# ESP32_S3.net
KiCad netlist of a schematic drawn in Altium Designer
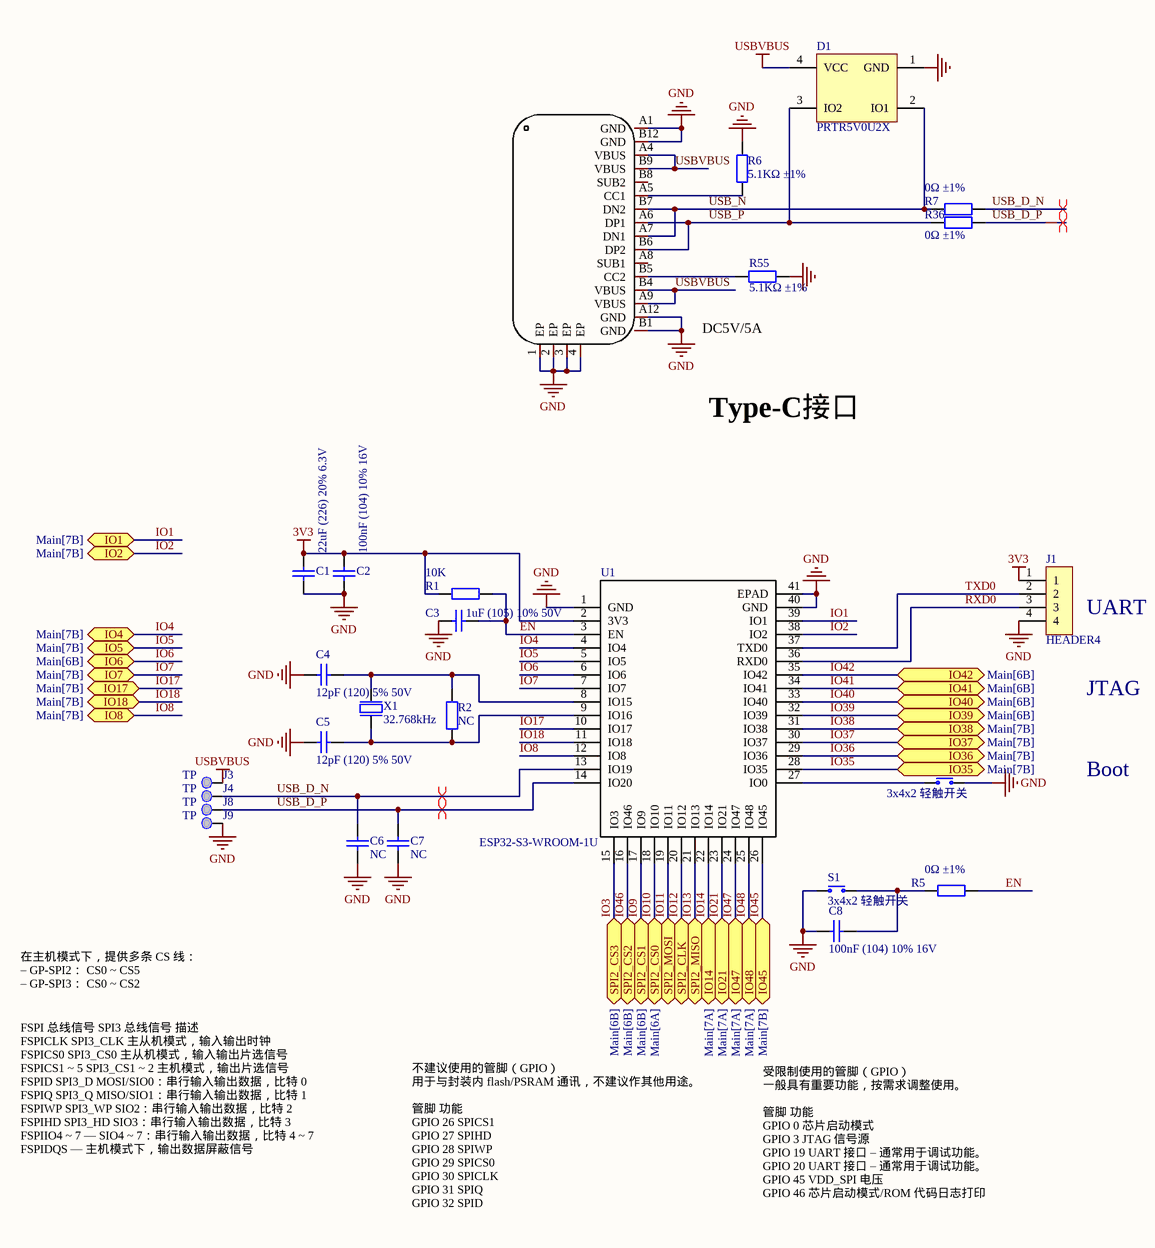
[diagram p0: ESP32_S3.SchDoc]

(export (version "E")
  (design (tool "Eeschema 10.0.6"))
  (components
    (comp (ref "C1")
      (value "22uF (226) 20% 6.3V")
      (footprint "0402_C")
      (description "贴片电容")
      (libsource (lib "Cap") (part "0603 22uF (226) 20% 6.3V"))
    )
    (comp (ref "C2")
      (value "100nF (104) 10% 16V")
      (footprint "0201_C")
      (description "贴片电容")
      (libsource (lib "Cap") (part "0402 100nF (104) 10% 16V"))
    )
    (comp (ref "C3")
      (value "1uF (105) 10% 50V")
      (footprint "0201_C")
      (description "贴片电容")
      (libsource (lib "Cap") (part "0603 1uF (105) 10% 50V"))
    )
    (comp (ref "C4")
      (value "12pF (120) 5% 50V")
      (footprint "0201_C")
      (description "贴片电容")
      (libsource (lib "Cap") (part "0402 12pF (120) 5% 50V"))
    )
    (comp (ref "C5")
      (value "12pF (120) 5% 50V")
      (footprint "0201_C")
      (description "贴片电容")
      (libsource (lib "Cap") (part "0402 12pF (120) 5% 50V"))
    )
    (comp (ref "C6")
      (value "NC")
      (footprint "0402_C")
      (description "贴片电容")
      (libsource (lib "Cap") (part "0402 12pF (120) 5% 50V"))
    )
    (comp (ref "C7")
      (value "NC")
      (footprint "0402_C")
      (description "贴片电容")
      (libsource (lib "Cap") (part "0402 12pF (120) 5% 50V"))
    )
    (comp (ref "C8")
      (value "100nF (104) 10% 16V")
      (footprint "0201_C")
      (description "贴片电容")
      (libsource (lib "Cap") (part "0402 100nF (104) 10% 16V"))
    )
    (comp (ref "D1")
      (value "PRTR5V0U2X")
      (footprint "SOT190P230X110-4L")
      (description "Ultra low capacitance double rail-to-rail ESD protection diode")
      (fields
        (field (name "MANUFACTURER") "NXP")
        (field (name "2ND SOURCE PART NUMBER") "152-4157")
        (field (name "PUBLISHER") "Nordic Semiconductor")
      )
      (libsource (lib "Nordic Discrete DB") (part "PRTR5V0U2X"))
    )
    (comp (ref "J1")
      (value "HEADER4")
      (footprint "HEADER4_2.54MM_排针")
      (libsource (lib "RFID") (part "HEADER4"))
    )
    (comp (ref "J3") (value "TP") (footprint "TEST_Point") (libsource (lib "RFID") (part "TestPad")))
    (comp (ref "J4") (value "TP") (footprint "TEST_Point") (libsource (lib "RFID") (part "TestPad")))
    (comp (ref "J8") (value "TP") (footprint "TEST_Point") (libsource (lib "RFID") (part "TestPad")))
    (comp (ref "J9") (value "TP") (footprint "TEST_Point") (libsource (lib "RFID") (part "TestPad")))
    (comp (ref "R1")
      (value "10K")
      (footprint "0201_R")
      (description "贴片电阻")
      (libsource (lib "RES") (part "0402 10KΩ (1002) 1%"))
    )
    (comp (ref "R2")
      (value "NC")
      (footprint "0402_R")
      (description "贴片电阻")
      (libsource (lib "") (part "0402 10KΩ (1002) 1%_1"))
    )
    (comp (ref "R5")
      (value "0Ω ±1%")
      (footprint "0402_R")
      (description "贴片电阻")
      (libsource (lib "RES") (part "0402 0Ω (0R0) 1%"))
    )
    (comp (ref "R6")
      (value "5.1KΩ ±1%")
      (footprint "0402_R")
      (description "贴片电阻")
      (libsource (lib "Miscellaneous Devices LC") (part "0402 5.1KΩ (5101) 1%"))
    )
    (comp (ref "R7")
      (value "0Ω ±1%")
      (footprint "0402_R")
      (description "贴片电阻")
      (libsource (lib "RES") (part "0402 0Ω (0R0) 1%"))
    )
    (comp (ref "R36")
      (value "0Ω ±1%")
      (footprint "0402_R")
      (description "贴片电阻")
      (libsource (lib "RES") (part "0402 0Ω (0R0) 1%"))
    )
    (comp (ref "R55")
      (value "5.1KΩ ±1%")
      (footprint "0402_R")
      (description "贴片电阻")
      (libsource (lib "") (part "0402 5.1KΩ (5101) 1%_1"))
    )
    (comp (ref "S1")
      (value "3x4x2 轻触开关")
      (footprint "KEY_3x4X2包脚U型")
      (libsource (lib "RFID") (part "SW-PB_包脚U型小乌龟"))
    )
    (comp (ref "S3")
      (value "3x4x2 轻触开关")
      (footprint "KEY_3x4X2包脚U型")
      (libsource (lib "RFID") (part "SW-PB_包脚U型小乌龟"))
    )
    (comp (ref "U1")
      (value "ESP32-S3-WROOM-1U")
      (footprint "WIRELM-SMD_ESP32-S3-WROOM-1U")
      (libsource (lib "RFID") (part "ESP32-S3-WROOM-1U"))
    )
    (comp (ref "USB1")
      (value "KH-TYPE-C-16P")
      (footprint "USB-C-SMD_KH-TYPE-C-16P")
      (libsource (lib "RFID") (part "KH-TYPE-C-16P"))
    )
    (comp (ref "X1")
      (value "32.768kHz")
      (footprint "XTAL_3215")
      (description "XTAL SMD 3215, 32.768kHz, Cl=9pF, Total Tol: ±50ppm")
      (fields (field (name "PART NUMBER") "XTAL_SMD3215_32.768kHz_9pF_General"))
      (libsource (lib "AltiumLib") (part "XTAL_2-pin"))
    )
  )
  (nets
    (net (code "1") (name "/EN") (class "Default")
      (node (ref "C3") (pin "2") (pinfunction "2_2") (pintype "passive"))
      (node (ref "R1") (pin "1") (pinfunction "1_1") (pintype "passive"))
      (node (ref "R5") (pin "2") (pinfunction "2_2") (pintype "passive"))
      (node (ref "U1") (pin "3") (pinfunction "EN_3") (pintype "passive"))
    )
    (net (code "2") (name "/IO1") (class "Default")
      (node (ref "U1") (pin "39") (pinfunction "IO1_39") (pintype "passive"))
    )
    (net (code "3") (name "/IO2") (class "Default")
      (node (ref "U1") (pin "38") (pinfunction "IO2_38") (pintype "passive"))
    )
    (net (code "4") (name "/IO3") (class "Default")
      (node (ref "U1") (pin "15") (pinfunction "IO3_15") (pintype "passive"))
    )
    (net (code "5") (name "/IO4") (class "Default")
      (node (ref "U1") (pin "4") (pinfunction "IO4_4") (pintype "passive"))
    )
    (net (code "6") (name "/IO5") (class "Default")
      (node (ref "U1") (pin "5") (pinfunction "IO5_5") (pintype "passive"))
    )
    (net (code "7") (name "/IO6") (class "Default")
      (node (ref "U1") (pin "6") (pinfunction "IO6_6") (pintype "passive"))
    )
    (net (code "8") (name "/IO7") (class "Default")
      (node (ref "U1") (pin "7") (pinfunction "IO7_7") (pintype "passive"))
    )
    (net (code "9") (name "/IO8") (class "Default")
      (node (ref "U1") (pin "12") (pinfunction "IO8_12") (pintype "passive"))
    )
    (net (code "10") (name "/IO9") (class "Default")
      (node (ref "U1") (pin "17") (pinfunction "IO9_17") (pintype "passive"))
    )
    (net (code "11") (name "/IO10") (class "Default")
      (node (ref "U1") (pin "18") (pinfunction "IO10_18") (pintype "passive"))
    )
    (net (code "12") (name "/IO11") (class "Default")
      (node (ref "U1") (pin "19") (pinfunction "IO11_19") (pintype "passive"))
    )
    (net (code "13") (name "/IO12") (class "Default")
      (node (ref "U1") (pin "20") (pinfunction "IO12_20") (pintype "passive"))
    )
    (net (code "14") (name "/IO13") (class "Default")
      (node (ref "U1") (pin "21") (pinfunction "IO13_21") (pintype "passive"))
    )
    (net (code "15") (name "/IO14") (class "Default")
      (node (ref "U1") (pin "22") (pinfunction "IO14_22") (pintype "passive"))
    )
    (net (code "16") (name "/IO17") (class "Default")
      (node (ref "U1") (pin "10") (pinfunction "IO17_10") (pintype "passive"))
    )
    (net (code "17") (name "/IO18") (class "Default")
      (node (ref "U1") (pin "11") (pinfunction "IO18_11") (pintype "passive"))
    )
    (net (code "18") (name "/IO21") (class "Default")
      (node (ref "U1") (pin "23") (pinfunction "IO21_23") (pintype "passive"))
    )
    (net (code "19") (name "/IO35") (class "Default")
      (node (ref "U1") (pin "28") (pinfunction "IO35_28") (pintype "passive"))
    )
    (net (code "20") (name "/IO36") (class "Default")
      (node (ref "U1") (pin "29") (pinfunction "IO36_29") (pintype "passive"))
    )
    (net (code "21") (name "/IO37") (class "Default")
      (node (ref "U1") (pin "30") (pinfunction "IO37_30") (pintype "passive"))
    )
    (net (code "22") (name "/IO38") (class "Default")
      (node (ref "U1") (pin "31") (pinfunction "IO38_31") (pintype "passive"))
    )
    (net (code "23") (name "/IO39") (class "Default")
      (node (ref "U1") (pin "32") (pinfunction "IO39_32") (pintype "passive"))
    )
    (net (code "24") (name "/IO40") (class "Default")
      (node (ref "U1") (pin "33") (pinfunction "IO40_33") (pintype "passive"))
    )
    (net (code "25") (name "/IO41") (class "Default")
      (node (ref "U1") (pin "34") (pinfunction "IO41_34") (pintype "passive"))
    )
    (net (code "26") (name "/IO42") (class "Default")
      (node (ref "U1") (pin "35") (pinfunction "IO42_35") (pintype "passive"))
    )
    (net (code "27") (name "/IO45") (class "Default")
      (node (ref "U1") (pin "26") (pinfunction "IO45_26") (pintype "passive"))
    )
    (net (code "28") (name "/IO46") (class "Default")
      (node (ref "U1") (pin "16") (pinfunction "IO46_16") (pintype "passive"))
    )
    (net (code "29") (name "/IO47") (class "Default")
      (node (ref "U1") (pin "24") (pinfunction "IO47_24") (pintype "passive"))
    )
    (net (code "30") (name "/IO48") (class "Default")
      (node (ref "U1") (pin "25") (pinfunction "IO48_25") (pintype "passive"))
    )
    (net (code "31") (name "/RXD0") (class "Default")
      (node (ref "J1") (pin "3") (pinfunction "3_3") (pintype "power_in"))
      (node (ref "U1") (pin "36") (pinfunction "RXD0_36") (pintype "passive"))
    )
    (net (code "32") (name "/TXD0") (class "Default")
      (node (ref "J1") (pin "2") (pinfunction "2_2") (pintype "power_in"))
      (node (ref "U1") (pin "37") (pinfunction "TXD0_37") (pintype "passive"))
    )
    (net (code "33") (name "/USB_D_N") (class "Default")
      (node (ref "C6") (pin "2") (pinfunction "2_2") (pintype "passive"))
      (node (ref "J4") (pin "1") (pinfunction "1_1") (pintype "power_in"))
      (node (ref "R7") (pin "2") (pinfunction "2_2") (pintype "passive"))
      (node (ref "U1") (pin "13") (pinfunction "IO19_13") (pintype "passive"))
    )
    (net (code "34") (name "/USB_D_P") (class "Default")
      (node (ref "C7") (pin "2") (pinfunction "2_2") (pintype "passive"))
      (node (ref "J8") (pin "1") (pinfunction "1_1") (pintype "power_in"))
      (node (ref "R36") (pin "2") (pinfunction "2_2") (pintype "passive"))
      (node (ref "U1") (pin "14") (pinfunction "IO20_14") (pintype "passive"))
    )
    (net (code "35") (name "/USB_N") (class "Default")
      (node (ref "D1") (pin "2") (pinfunction "IO1_2") (pintype "passive"))
      (node (ref "R7") (pin "1") (pinfunction "1_1") (pintype "passive"))
      (node (ref "USB1") (pin "A7") (pinfunction "DN1_A7") (pintype "passive"))
      (node (ref "USB1") (pin "B7") (pinfunction "DN2_B7") (pintype "passive"))
    )
    (net (code "36") (name "/USB_P") (class "Default")
      (node (ref "D1") (pin "3") (pinfunction "IO2_3") (pintype "passive"))
      (node (ref "R36") (pin "1") (pinfunction "1_1") (pintype "passive"))
      (node (ref "USB1") (pin "A6") (pinfunction "DP1_A6") (pintype "passive"))
      (node (ref "USB1") (pin "B6") (pinfunction "DP2_B6") (pintype "passive"))
    )
    (net (code "37") (name "3V3") (class "Default")
      (node (ref "C1") (pin "2") (pinfunction "2_2") (pintype "passive"))
      (node (ref "C2") (pin "2") (pinfunction "2_2") (pintype "passive"))
      (node (ref "J1") (pin "1") (pinfunction "1_1") (pintype "power_in"))
      (node (ref "R1") (pin "2") (pinfunction "2_2") (pintype "passive"))
      (node (ref "U1") (pin "2") (pinfunction "3V3_2") (pintype "passive"))
    )
    (net (code "38") (name "GND") (class "Default")
      (node (ref "C1") (pin "1") (pinfunction "1_1") (pintype "passive"))
      (node (ref "C2") (pin "1") (pinfunction "1_1") (pintype "passive"))
      (node (ref "C3") (pin "1") (pinfunction "1_1") (pintype "passive"))
      (node (ref "C4") (pin "1") (pinfunction "1_1") (pintype "passive"))
      (node (ref "C5") (pin "1") (pinfunction "1_1") (pintype "passive"))
      (node (ref "C6") (pin "1") (pinfunction "1_1") (pintype "passive"))
      (node (ref "C7") (pin "1") (pinfunction "1_1") (pintype "passive"))
      (node (ref "C8") (pin "2") (pinfunction "2_2") (pintype "passive"))
      (node (ref "D1") (pin "1") (pinfunction "GND_1") (pintype "passive"))
      (node (ref "J1") (pin "4") (pinfunction "4_4") (pintype "power_in"))
      (node (ref "J9") (pin "1") (pinfunction "1_1") (pintype "power_in"))
      (node (ref "R55") (pin "2") (pinfunction "2_2") (pintype "passive"))
      (node (ref "R6") (pin "1") (pinfunction "1_1") (pintype "passive"))
      (node (ref "S1") (pin "2") (pinfunction "2_2") (pintype "passive"))
      (node (ref "S3") (pin "1") (pinfunction "1_1") (pintype "passive"))
      (node (ref "U1") (pin "1") (pinfunction "GND_1") (pintype "passive"))
      (node (ref "U1") (pin "40") (pinfunction "GND_40") (pintype "passive"))
      (node (ref "U1") (pin "41") (pinfunction "EPAD_41") (pintype "passive"))
      (node (ref "USB1") (pin "1") (pinfunction "EP_1") (pintype "passive"))
      (node (ref "USB1") (pin "2") (pinfunction "EP_2") (pintype "passive"))
      (node (ref "USB1") (pin "3") (pinfunction "EP_3") (pintype "passive"))
      (node (ref "USB1") (pin "4") (pinfunction "EP_4") (pintype "passive"))
      (node (ref "USB1") (pin "A1") (pinfunction "GND_A1") (pintype "passive"))
      (node (ref "USB1") (pin "A12") (pinfunction "GND_A12") (pintype "passive"))
      (node (ref "USB1") (pin "B1") (pinfunction "GND_B1") (pintype "passive"))
      (node (ref "USB1") (pin "B12") (pinfunction "GND_B12") (pintype "passive"))
    )
    (net (code "39") (name "Net-(C8-Pad1)") (class "Default")
      (node (ref "C8") (pin "1") (pinfunction "1_1") (pintype "passive"))
      (node (ref "R5") (pin "1") (pinfunction "1_1") (pintype "passive"))
      (node (ref "S1") (pin "1") (pinfunction "1_1") (pintype "passive"))
    )
    (net (code "40") (name "Net-(U1-IO0)") (class "Default")
      (node (ref "S3") (pin "2") (pinfunction "2_2") (pintype "passive"))
      (node (ref "U1") (pin "27") (pinfunction "IO0_27") (pintype "passive"))
    )
    (net (code "41") (name "Net-(U1-IO15)") (class "Default")
      (node (ref "C4") (pin "2") (pinfunction "2_2") (pintype "passive"))
      (node (ref "R2") (pin "2") (pinfunction "2_2") (pintype "passive"))
      (node (ref "U1") (pin "8") (pinfunction "IO15_8") (pintype "passive"))
      (node (ref "X1") (pin "1") (pinfunction "inp_1") (pintype "passive"))
    )
    (net (code "42") (name "Net-(U1-IO16)") (class "Default")
      (node (ref "C5") (pin "2") (pinfunction "2_2") (pintype "passive"))
      (node (ref "R2") (pin "1") (pinfunction "1_1") (pintype "passive"))
      (node (ref "U1") (pin "9") (pinfunction "IO16_9") (pintype "passive"))
      (node (ref "X1") (pin "2") (pinfunction "out_2") (pintype "passive"))
    )
    (net (code "43") (name "Net-(USB1-CC1)") (class "Default")
      (node (ref "R6") (pin "2") (pinfunction "2_2") (pintype "passive"))
      (node (ref "USB1") (pin "A5") (pinfunction "CC1_A5") (pintype "passive"))
    )
    (net (code "44") (name "Net-(USB1-CC2)") (class "Default")
      (node (ref "R55") (pin "1") (pinfunction "1_1") (pintype "passive"))
      (node (ref "USB1") (pin "B5") (pinfunction "CC2_B5") (pintype "passive"))
    )
    (net (code "45") (name "USBVBUS") (class "Default")
      (node (ref "D1") (pin "4") (pinfunction "VCC_4") (pintype "passive"))
      (node (ref "J3") (pin "1") (pinfunction "1_1") (pintype "power_in"))
      (node (ref "USB1") (pin "A4") (pinfunction "VBUS_A4") (pintype "passive"))
      (node (ref "USB1") (pin "A9") (pinfunction "VBUS_A9") (pintype "passive"))
      (node (ref "USB1") (pin "B4") (pinfunction "VBUS_B4") (pintype "passive"))
      (node (ref "USB1") (pin "B9") (pinfunction "VBUS_B9") (pintype "passive"))
    )
    (net (code "46") (name "unconnected-(USB1-SUB1-PadA8)") (class "Default")
      (node (ref "USB1") (pin "A8") (pinfunction "SUB1_A8") (pintype "passive"))
    )
    (net (code "47") (name "unconnected-(USB1-SUB2-PadB8)") (class "Default")
      (node (ref "USB1") (pin "B8") (pinfunction "SUB2_B8") (pintype "passive"))
    )
  )
)
